# AD8232_TMP136.net
KiCad netlist of a schematic drawn in Altium Designer
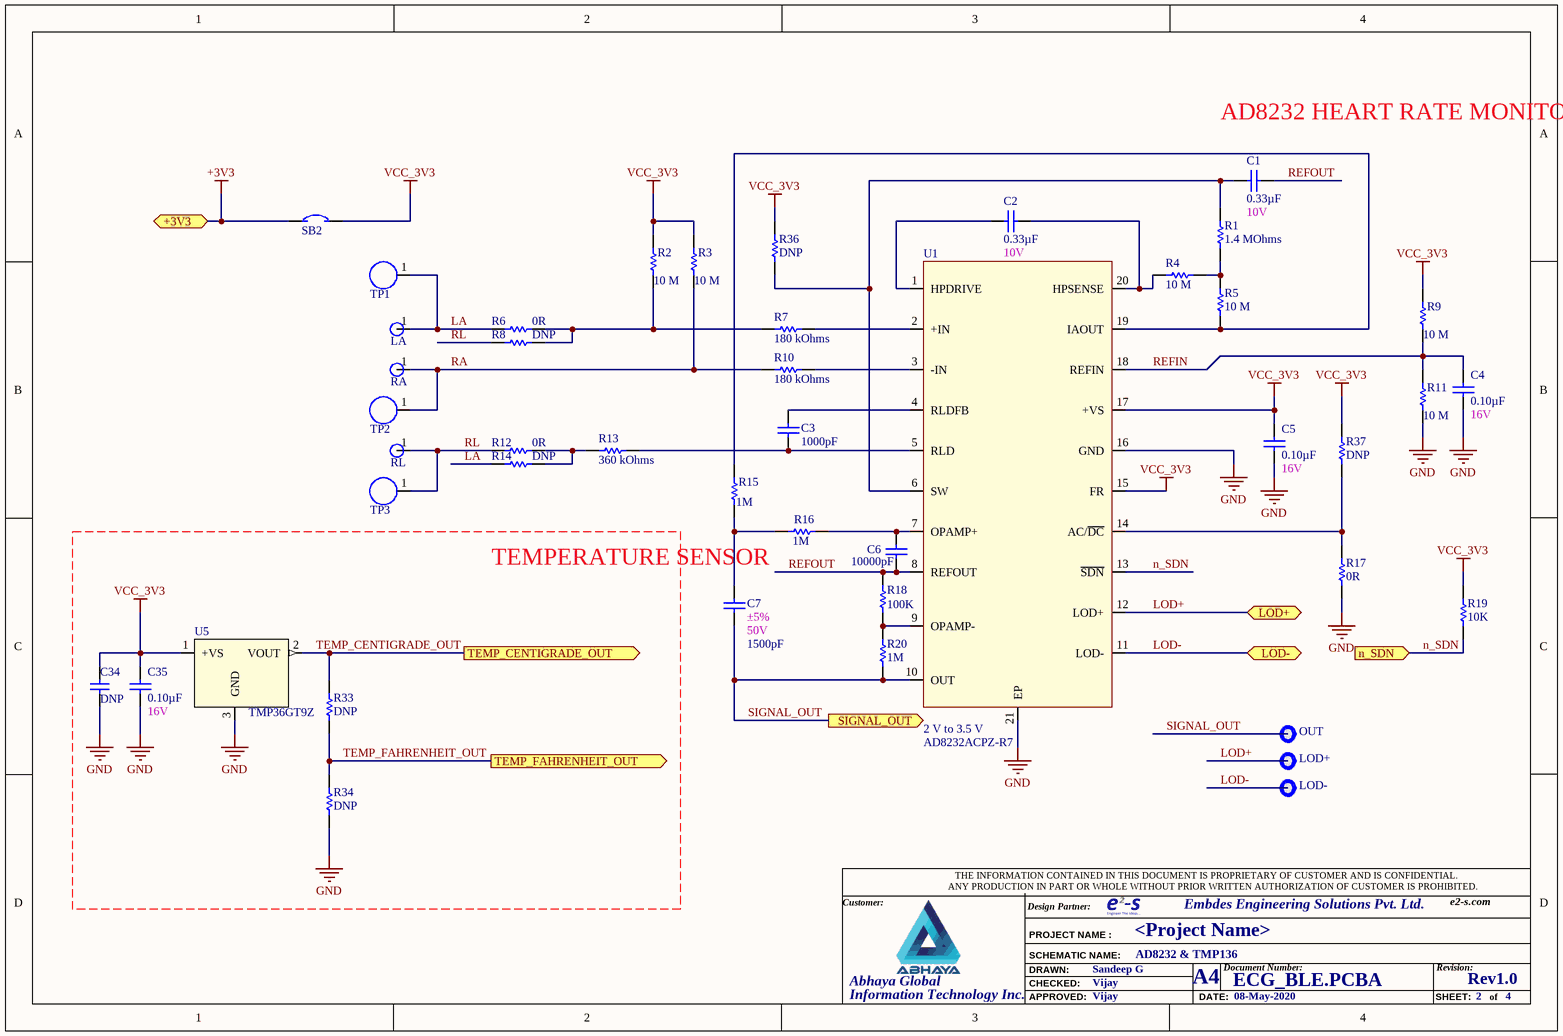
[diagram p0: AD8232 & TMP136.SchDoc]

(export (version "E")
  (design (tool "Eeschema 10.0.6"))
  (components
    (comp (ref "C1")
      (value "0.33µF")
      (footprint "SMDC0402")
      (description "CAP CER 0.33UF 10V X5R 0402")
      (fields
        (field (name "MANUFACTURER") "Samsung Electro-Mechanics")
        (field (name "MANUFACTURER PART NUMBER") "CL05A334KP5NNNC")
        (field (name "1ST AUXILIARY FIELD") "10V")
      )
      (libsource (lib "Master_ Library") (part "ECA0U33L10V0-SB"))
    )
    (comp (ref "C2")
      (value "0.33µF")
      (footprint "SMDC0402")
      (description "CAP CER 0.33UF 10V X5R 0402")
      (fields
        (field (name "MANUFACTURER") "Samsung Electro-Mechanics")
        (field (name "MANUFACTURER PART NUMBER") "CL05A334KP5NNNC")
        (field (name "1ST AUXILIARY FIELD") "10V")
      )
      (libsource (lib "Master_ Library") (part "ECA0U33L10V0-SB"))
    )
    (comp (ref "C3")
      (value "1000pF")
      (footprint "SMDC0402")
      (description "CAP CER 1000PF 50V X7R 0402")
      (fields
        (field (name "MANUFACTURER") "KEMET")
        (field (name "MANUFACTURER PART NUMBER") "C0402C102J5RACTU")
      )
      (libsource (lib "Master_ Library") (part "ECA1N00K50V0-SB"))
    )
    (comp (ref "C4")
      (value "0.10µF")
      (footprint "SMDC0402")
      (description "CAP CER 0.1UF 16V X7R 0402")
      (fields
        (field (name "MANUFACTURER") "Samsung Electro-Mechanics America, Inc.")
        (field (name "MANUFACTURER PART NUMBER") "CL05B104KO5NNNC")
        (field (name "1ST AUXILIARY FIELD") "16V")
      )
      (libsource (lib "Master_ Library") (part "ECA0U10K16V0-1-SB"))
    )
    (comp (ref "C5")
      (value "0.10µF")
      (footprint "SMDC0402")
      (description "CAP CER 0.1UF 16V X7R 0402")
      (fields
        (field (name "MANUFACTURER") "Samsung Electro-Mechanics America, Inc.")
        (field (name "MANUFACTURER PART NUMBER") "CL05B104KO5NNNC")
        (field (name "1ST AUXILIARY FIELD") "16V")
      )
      (libsource (lib "Master_ Library") (part "ECA0U10K16V0-1-SB"))
    )
    (comp (ref "C6")
      (value "10000pF")
      (footprint "SMDCC0402")
      (description "CAP CER 10000PF 50V X7R 0402")
      (fields
        (field (name "MANUFACTURER PART NUMBER") "C0402C103J5RACTU")
        (field (name "MANUFACTURER") "Samsung Electro-Mechanics America, Inc.")
      )
      (libsource (lib "Master_ Library") (part "ECA10N0K50V0-SB"))
    )
    (comp (ref "C7")
      (value "1500pF")
      (footprint "SMDC0402")
      (description "CAP CER 1500PF 50V X7R 0402")
      (fields
        (field (name "MANUFACTURER") "Yageo")
        (field (name "VENDOR PART NUMBER") "311-3763-1-ND")
        (field (name "2ND AUXILIARY FIELD") "±5%")
        (field (name "1ST AUXILIARY FIELD") "50V")
      )
      (libsource (lib "Master_ Library") (part "ECA1N50K50V0-SB"))
    )
    (comp (ref "C34")
      (value "DNP")
      (footprint "SMDC0402")
      (description "CAP CER 2.2UF 10V JB 0402")
      (fields
        (field (name "INTERNAL PART NUMBER") "ECA2U20L10V-SB")
        (field (name "MANUFACTURER") "TDK Corporation")
      )
      (libsource (lib "Master_ Library") (part "ECA2U20L10V-SB"))
    )
    (comp (ref "C35")
      (value "0.10µF")
      (footprint "SMDC0402")
      (description "CAP CER 0.1UF 16V X7R 0402")
      (fields
        (field (name "MANUFACTURER") "Samsung Electro-Mechanics America, Inc.")
        (field (name "MANUFACTURER PART NUMBER") "CL05B104KO5NNNC")
        (field (name "1ST AUXILIARY FIELD") "16V")
      )
      (libsource (lib "Master_ Library") (part "ECA0U10K16V0-1-SB"))
    )
    (comp (ref "LA")
      (value "Test Point- 1.02mm Hole, 1.52mm Round Pad")
      (footprint "TP_1.02X1.52MM_TH")
      (fields (field (name "INTERNAL PART NUMBER") "EMS-TP_1X1.52MM_TH"))
      (libsource (lib "Integrated_Library (1)") (part "EMS-TP_1X1.52MM_TH"))
    )
    (comp (ref "LOD+")
      (value "TEST POINT")
      (footprint "TP_40X40")
      (fields (field (name "INTERNAL PART NUMBER") "EMS-TP40X40-S"))
      (libsource (lib "Integrated_Master_Library") (part "EMS-TP40X40-S"))
    )
    (comp (ref "LOD-")
      (value "TEST POINT")
      (footprint "TP_40X40")
      (fields (field (name "INTERNAL PART NUMBER") "EMS-TP40X40-S"))
      (libsource (lib "Integrated_Master_Library") (part "EMS-TP40X40-S"))
    )
    (comp (ref "OUT")
      (value "TEST POINT")
      (footprint "TP_40X40")
      (fields (field (name "INTERNAL PART NUMBER") "EMS-TP40X40-S"))
      (libsource (lib "Integrated_Master_Library") (part "EMS-TP40X40-S"))
    )
    (comp (ref "R1")
      (value "1.4 MOhms")
      (footprint "SMDR0402")
      (description "RES 1.4M OHM 1% 1/16W 0402")
      (fields
        (field (name "MANUFACTURER") "Stackpole Electronics Inc")
        (field (name "VENDOR PART NUMBER") "RMCF0402FT1M40CT-ND")
      )
      (libsource (lib "Master_ Library") (part "ERE1M40G116-SB"))
    )
    (comp (ref "R2")
      (value "10 M")
      (footprint "SMDR0402")
      (description "RES SMD 10M OHM 5% 1/10W 0402")
      (fields
        (field (name "MANUFACTURER PART NUMBER") "ERJ-2GEJ106X")
        (field (name "MANUFACTURER") "Panasonic Electronic Components")
      )
      (libsource (lib "Master_ Library") (part "ERE10M0K110-SB"))
    )
    (comp (ref "R3")
      (value "10 M")
      (footprint "SMDR0402")
      (description "RES SMD 10M OHM 5% 1/10W 0402")
      (fields
        (field (name "MANUFACTURER PART NUMBER") "ERJ-2GEJ106X")
        (field (name "MANUFACTURER") "Panasonic Electronic Components")
      )
      (libsource (lib "Master_ Library") (part "ERE10M0K110-SB"))
    )
    (comp (ref "R4")
      (value "10 M")
      (footprint "SMDR0402")
      (description "RES SMD 10M OHM 5% 1/10W 0402")
      (fields
        (field (name "MANUFACTURER PART NUMBER") "ERJ-2GEJ106X")
        (field (name "MANUFACTURER") "Panasonic Electronic Components")
      )
      (libsource (lib "Master_ Library") (part "ERE10M0K110-SB"))
    )
    (comp (ref "R5")
      (value "10 M")
      (footprint "SMDR0402")
      (description "RES SMD 10M OHM 5% 1/10W 0402")
      (fields
        (field (name "MANUFACTURER PART NUMBER") "ERJ-2GEJ106X")
        (field (name "MANUFACTURER") "Panasonic Electronic Components")
      )
      (libsource (lib "Master_ Library") (part "ERE10M0K110-SB"))
    )
    (comp (ref "R6")
      (value "0R")
      (footprint "SMDR0402")
      (description "RES SMD 0.0OHM JUMPER 1/10W 0402")
      (fields
        (field (name "MANUFACTURER") "Panasonic Electronic Components")
        (field (name "VENDOR PART NUMBER") "P0.0JCT-ND")
      )
      (libsource (lib "Integrated_Master_Library") (part "ERE0R00110-SB"))
    )
    (comp (ref "R7")
      (value "180 kOhms")
      (footprint "SMDR0402")
      (description "RES SMD 180K OHM 1% 1/16W 0402")
      (fields (field (name "MANUFACTURER") "Yageo") (field (name "VENDOR PART NUMBER") "311-180KLRCT-ND"))
      (libsource (lib "Master_ Library") (part "ERE180KG116-SB"))
    )
    (comp (ref "R8")
      (value "DNP")
      (footprint "SMDR0402")
      (description "RES SMD 0.0OHM JUMPER 1/10W 0402")
      (fields
        (field (name "MANUFACTURER") "Panasonic Electronic Components")
        (field (name "VENDOR PART NUMBER") "P0.0JCT-ND")
      )
      (libsource (lib "Integrated_Master_Library") (part "ERE0R00110-SB"))
    )
    (comp (ref "R9")
      (value "10 M")
      (footprint "SMDR0402")
      (description "RES SMD 10M OHM 5% 1/10W 0402")
      (fields
        (field (name "MANUFACTURER PART NUMBER") "ERJ-2GEJ106X")
        (field (name "MANUFACTURER") "Panasonic Electronic Components")
      )
      (libsource (lib "Master_ Library") (part "ERE10M0K110-SB"))
    )
    (comp (ref "R10")
      (value "180 kOhms")
      (footprint "SMDR0402")
      (description "RES SMD 180K OHM 1% 1/16W 0402")
      (fields (field (name "MANUFACTURER") "Yageo") (field (name "VENDOR PART NUMBER") "311-180KLRCT-ND"))
      (libsource (lib "Master_ Library") (part "ERE180KG116-SB"))
    )
    (comp (ref "R11")
      (value "10 M")
      (footprint "SMDR0402")
      (description "RES SMD 10M OHM 5% 1/10W 0402")
      (fields
        (field (name "MANUFACTURER PART NUMBER") "ERJ-2GEJ106X")
        (field (name "MANUFACTURER") "Panasonic Electronic Components")
      )
      (libsource (lib "Master_ Library") (part "ERE10M0K110-SB"))
    )
    (comp (ref "R12")
      (value "0R")
      (footprint "SMDR0402")
      (description "RES SMD 0.0OHM JUMPER 1/10W 0402")
      (fields
        (field (name "MANUFACTURER") "Panasonic Electronic Components")
        (field (name "VENDOR PART NUMBER") "P0.0JCT-ND")
      )
      (libsource (lib "Integrated_Master_Library") (part "ERE0R00110-SB"))
    )
    (comp (ref "R13")
      (value "360 kOhms")
      (footprint "SMDR0402")
      (description "RES SMD 360K OHM 1% 1/10W 0402")
      (fields
        (field (name "MANUFACTURER") "Panasonic Electronic Components")
        (field (name "VENDOR PART NUMBER") "P360KLCT-ND")
      )
      (libsource (lib "Master_ Library") (part "ERE360KG110-SB"))
    )
    (comp (ref "R14")
      (value "DNP")
      (footprint "SMDR0402")
      (description "RES SMD 0.0OHM JUMPER 1/10W 0402")
      (fields
        (field (name "MANUFACTURER") "Panasonic Electronic Components")
        (field (name "VENDOR PART NUMBER") "P0.0JCT-ND")
      )
      (libsource (lib "Integrated_Master_Library") (part "ERE0R00110-SB"))
    )
    (comp (ref "R15")
      (value "1M")
      (footprint "SMDR0402")
      (description "RES SMD 1M OHM 1% 1/10W 0402")
      (fields
        (field (name "MANUFACTURER PART NUMBER") "ERJ-2RKF1004X")
        (field (name "MANUFACTURER") "Panasonic Electronic Components")
      )
      (libsource (lib "Master_ Library") (part "ERE1M00G110-SB"))
    )
    (comp (ref "R16")
      (value "1M")
      (footprint "SMDR0402")
      (description "RES SMD 1M OHM 1% 1/10W 0402")
      (fields
        (field (name "MANUFACTURER PART NUMBER") "ERJ-2RKF1004X")
        (field (name "MANUFACTURER") "Panasonic Electronic Components")
      )
      (libsource (lib "Master_ Library") (part "ERE1M00G110-SB"))
    )
    (comp (ref "R17")
      (value "0R")
      (footprint "SMDR0402")
      (description "RES SMD 0.0OHM JUMPER 1/10W 0402")
      (fields
        (field (name "MANUFACTURER") "Panasonic Electronic Components")
        (field (name "VENDOR PART NUMBER") "P0.0JCT-ND")
      )
      (libsource (lib "Integrated_Master_Library") (part "ERE0R00110-SB"))
    )
    (comp (ref "R18")
      (value "100K")
      (footprint "SMDRC0402")
      (description "RES SMD 100K OHM 1% 1/10W 0402")
      (fields
        (field (name "MANUFACTURER PART NUMBER") "ERJ-2RKF1003X")
        (field (name "MANUFACTURER") "Panasonic Electronic Components")
      )
      (libsource (lib "Master_ Library") (part "ERE100KG110-SB"))
    )
    (comp (ref "R19")
      (value "10K")
      (footprint "SMDR0402")
      (description "RES SMD 10K OHM 1% 1/10W 0402")
      (fields
        (field (name "MANUFACTURER") "Panasonic Electronic Components")
        (field (name "INTERNAL PART NUMBER") "ERE10K0G110-SB")
      )
      (libsource (lib "Master_ Library") (part "ERE10K0G110-SB"))
    )
    (comp (ref "R20")
      (value "1M")
      (footprint "SMDR0402")
      (description "RES SMD 1M OHM 1% 1/10W 0402")
      (fields
        (field (name "MANUFACTURER PART NUMBER") "ERJ-2RKF1004X")
        (field (name "MANUFACTURER") "Panasonic Electronic Components")
      )
      (libsource (lib "Master_ Library") (part "ERE1M00G110-SB"))
    )
    (comp (ref "R33")
      (value "DNP")
      (footprint "SMDR0402")
      (description "RES 45.3K OHM 0.5% 1/16W 0402")
      (fields
        (field (name "MANUFACTURER") "Stackpole Electronics Inc")
        (field (name "VENDOR PART NUMBER") "RNCF0402DTE45K3CT-ND")
      )
      (libsource (lib "Master_ Library") (part "ERE45K3F116-SB"))
    )
    (comp (ref "R34")
      (value "DNP")
      (footprint "SMDR0402")
      (description "RES SMD 10K OHM 0.5% 1/16W 0402")
      (fields
        (field (name "MANUFACTURER") "Panasonic Electronic Components")
        (field (name "VENDOR PART NUMBER") "P15984CT-ND")
      )
      (libsource (lib "Master_ Library") (part "ERE10K0F116-SB"))
    )
    (comp (ref "R36")
      (value "DNP")
      (footprint "SMDR0402")
      (description "RES SMD 0.0OHM JUMPER 1/10W 0402")
      (fields
        (field (name "MANUFACTURER") "Panasonic Electronic Components")
        (field (name "VENDOR PART NUMBER") "P0.0JCT-ND")
      )
      (libsource (lib "Integrated_Master_Library") (part "ERE0R00110-SB"))
    )
    (comp (ref "R37")
      (value "DNP")
      (footprint "SMDR0402")
      (description "RES SMD 0.0OHM JUMPER 1/10W 0402")
      (fields
        (field (name "MANUFACTURER") "Panasonic Electronic Components")
        (field (name "VENDOR PART NUMBER") "P0.0JCT-ND")
      )
      (libsource (lib "Integrated_Master_Library") (part "ERE0R00110-SB"))
    )
    (comp (ref "RA")
      (value "Test Point- 1.02mm Hole, 1.52mm Round Pad")
      (footprint "TP_1.02X1.52MM_TH")
      (fields (field (name "INTERNAL PART NUMBER") "EMS-TP_1X1.52MM_TH"))
      (libsource (lib "Integrated_Library (1)") (part "EMS-TP_1X1.52MM_TH"))
    )
    (comp (ref "RL")
      (value "Test Point- 1.02mm Hole, 1.52mm Round Pad")
      (footprint "TP_1.02X1.52MM_TH")
      (fields (field (name "INTERNAL PART NUMBER") "EMS-TP_1X1.52MM_TH"))
      (libsource (lib "Integrated_Library (1)") (part "EMS-TP_1X1.52MM_TH"))
    )
    (comp (ref "SB2")
      (value "EMS_SB0805")
      (footprint "SB_0805")
      (libsource (lib "Masterlib_auto") (part "EMS_SB0805"))
    )
    (comp (ref "TP1")
      (value "Electrode point")
      (footprint "ELE-MH-6x8MM")
      (fields (field (name "INTERNAL PART NUMBER") "EMS-ELE_6X8MM_TH"))
      (libsource (lib "ECG_BLE") (part "EMS-ELE_6X8MM_TH"))
    )
    (comp (ref "TP2")
      (value "Electrode point")
      (footprint "ELE-MH-6x8MM")
      (fields (field (name "INTERNAL PART NUMBER") "EMS-ELE_6X8MM_TH"))
      (libsource (lib "ECG_BLE") (part "EMS-ELE_6X8MM_TH"))
    )
    (comp (ref "TP3")
      (value "Electrode point")
      (footprint "ELE-MH-6x8MM")
      (fields (field (name "INTERNAL PART NUMBER") "EMS-ELE_6X8MM_TH"))
      (libsource (lib "ECG_BLE") (part "EMS-ELE_6X8MM_TH"))
    )
    (comp (ref "U1")
      (value "AD8232ACPZ-R7")
      (footprint "QFN50P400X400X80_HS-21N")
      (description "Analog Front End - AFE ECG and HRM IC Single Lead")
      (fields
        (field (name "INTERNAL PART NUMBER") "EICADLFCSP-20-1862")
        (field (name "MANUFACTURER") "Analog Devices")
        (field (name "1ST AUXILIARY FIELD") "2 V to 3.5 V")
      )
      (libsource (lib "Master_ Library") (part "EICADLFCSP-20-1862"))
    )
    (comp (ref "U5")
      (value "TMP36GT9Z")
      (footprint "TO-226-AA")
      (description "SENSOR ANALOG -40C-125C TO92-3")
      (fields
        (field (name "INTERNAL PART NUMBER") "EICADTO92-3-1865")
        (field (name "MANUFACTURER") "Analog Devices Inc.")
      )
      (libsource (lib "Master_ Library") (part "EICADTO92-3-1865"))
    )
  )
  (nets
    (net (code "1") (name "+3V3") (class "Default")
      (node (ref "SB2") (pin "1") (pinfunction "1_1") (pintype "passive"))
    )
    (net (code "2") (name "/LA") (class "Default")
      (node (ref "LA") (pin "1") (pinfunction "1_1") (pintype "passive"))
      (node (ref "R14") (pin "1") (pinfunction "1_1") (pintype "passive"))
      (node (ref "R6") (pin "1") (pinfunction "1_1") (pintype "passive"))
      (node (ref "TP1") (pin "1") (pinfunction "1_1") (pintype "passive"))
    )
    (net (code "3") (name "/LOD+") (class "Default")
      (node (ref "LOD+") (pin "1") (pinfunction "1_1") (pintype "passive"))
      (node (ref "U1") (pin "12") (pinfunction "LOD+_12") (pintype "passive"))
    )
    (net (code "4") (name "/LOD-") (class "Default")
      (node (ref "LOD-") (pin "1") (pinfunction "1_1") (pintype "passive"))
      (node (ref "U1") (pin "11") (pinfunction "LOD-_11") (pintype "passive"))
    )
    (net (code "5") (name "/RA") (class "Default")
      (node (ref "R10") (pin "1") (pinfunction "1_1") (pintype "passive"))
      (node (ref "R3") (pin "1") (pinfunction "1_1") (pintype "passive"))
      (node (ref "RA") (pin "1") (pinfunction "1_1") (pintype "passive"))
      (node (ref "TP2") (pin "1") (pinfunction "1_1") (pintype "passive"))
    )
    (net (code "6") (name "/REFIN") (class "Default")
      (node (ref "C4") (pin "2") (pinfunction "2_2") (pintype "passive"))
      (node (ref "R11") (pin "2") (pinfunction "2_2") (pintype "passive"))
      (node (ref "R9") (pin "1") (pinfunction "1_1") (pintype "passive"))
      (node (ref "U1") (pin "18") (pinfunction "REFIN_18") (pintype "passive"))
    )
    (net (code "7") (name "/REFOUT") (class "Default")
      (node (ref "C1") (pin "2") (pinfunction "2_2") (pintype "passive"))
      (node (ref "C6") (pin "1") (pinfunction "1_1") (pintype "passive"))
      (node (ref "R18") (pin "1") (pinfunction "1_1") (pintype "passive"))
      (node (ref "U1") (pin "8") (pinfunction "REFOUT_8") (pintype "passive"))
    )
    (net (code "8") (name "/RL") (class "Default")
      (node (ref "R12") (pin "1") (pinfunction "1_1") (pintype "passive"))
      (node (ref "R8") (pin "1") (pinfunction "1_1") (pintype "passive"))
      (node (ref "RL") (pin "1") (pinfunction "1_1") (pintype "passive"))
      (node (ref "TP3") (pin "1") (pinfunction "1_1") (pintype "passive"))
    )
    (net (code "9") (name "/SIGNAL_OUT") (class "Default")
      (node (ref "C7") (pin "1") (pinfunction "1_1") (pintype "passive"))
      (node (ref "OUT") (pin "1") (pinfunction "1_1") (pintype "passive"))
      (node (ref "R20") (pin "2") (pinfunction "2_2") (pintype "passive"))
      (node (ref "U1") (pin "10") (pinfunction "OUT_10") (pintype "passive"))
    )
    (net (code "10") (name "/TEMP_CENTIGRADE_OUT") (class "Default")
      (node (ref "R33") (pin "2") (pinfunction "2_2") (pintype "passive"))
      (node (ref "U5") (pin "2") (pinfunction "VOUT_2") (pintype "output"))
    )
    (net (code "11") (name "/TEMP_FAHRENHEIT_OUT") (class "Default")
      (node (ref "R33") (pin "1") (pinfunction "1_1") (pintype "passive"))
      (node (ref "R34") (pin "2") (pinfunction "2_2") (pintype "passive"))
    )
    (net (code "12") (name "/n_SDN") (class "Default")
      (node (ref "R19") (pin "2") (pinfunction "2_2") (pintype "passive"))
      (node (ref "U1") (pin "13") (pinfunction "~{SDN}_13") (pintype "passive"))
    )
    (net (code "13") (name "GND") (class "Default")
      (node (ref "C34") (pin "1") (pinfunction "1_1") (pintype "passive"))
      (node (ref "C35") (pin "1") (pinfunction "1_1") (pintype "passive"))
      (node (ref "C4") (pin "1") (pinfunction "1_1") (pintype "passive"))
      (node (ref "C5") (pin "1") (pinfunction "1_1") (pintype "passive"))
      (node (ref "R11") (pin "1") (pinfunction "1_1") (pintype "passive"))
      (node (ref "R17") (pin "2") (pinfunction "2_2") (pintype "passive"))
      (node (ref "R34") (pin "1") (pinfunction "1_1") (pintype "passive"))
      (node (ref "U1") (pin "16") (pinfunction "GND_16") (pintype "passive"))
      (node (ref "U1") (pin "21") (pinfunction "EP_21") (pintype "passive"))
      (node (ref "U5") (pin "3") (pinfunction "GND_3") (pintype "power_in"))
    )
    (net (code "14") (name "Net-(C7-Pad2)") (class "Default")
      (node (ref "C7") (pin "2") (pinfunction "2_2") (pintype "passive"))
      (node (ref "R15") (pin "1") (pinfunction "1_1") (pintype "passive"))
      (node (ref "R16") (pin "2") (pinfunction "2_2") (pintype "passive"))
    )
    (net (code "15") (name "Net-(R1-Pad1)") (class "Default")
      (node (ref "R1") (pin "1") (pinfunction "1_1") (pintype "passive"))
      (node (ref "R4") (pin "1") (pinfunction "1_1") (pintype "passive"))
      (node (ref "R5") (pin "1") (pinfunction "1_1") (pintype "passive"))
    )
    (net (code "16") (name "Net-(R2-Pad1)") (class "Default")
      (node (ref "R2") (pin "1") (pinfunction "1_1") (pintype "passive"))
      (node (ref "R6") (pin "2") (pinfunction "2_2") (pintype "passive"))
      (node (ref "R7") (pin "1") (pinfunction "1_1") (pintype "passive"))
      (node (ref "R8") (pin "2") (pinfunction "2_2") (pintype "passive"))
    )
    (net (code "17") (name "Net-(R12-Pad2)") (class "Default")
      (node (ref "R12") (pin "2") (pinfunction "2_2") (pintype "passive"))
      (node (ref "R13") (pin "1") (pinfunction "1_1") (pintype "passive"))
      (node (ref "R14") (pin "2") (pinfunction "2_2") (pintype "passive"))
    )
    (net (code "18") (name "Net-(U1-+IN)") (class "Default")
      (node (ref "R7") (pin "2") (pinfunction "2_2") (pintype "passive"))
      (node (ref "U1") (pin "2") (pinfunction "+IN_2") (pintype "passive"))
    )
    (net (code "19") (name "Net-(U1--IN)") (class "Default")
      (node (ref "R10") (pin "2") (pinfunction "2_2") (pintype "passive"))
      (node (ref "U1") (pin "3") (pinfunction "-IN_3") (pintype "passive"))
    )
    (net (code "20") (name "Net-(U1-AC{slash}~{DC})") (class "Default")
      (node (ref "R17") (pin "1") (pinfunction "1_1") (pintype "passive"))
      (node (ref "R37") (pin "2") (pinfunction "2_2") (pintype "passive"))
      (node (ref "U1") (pin "14") (pinfunction "AC/~{DC}_14") (pintype "passive"))
    )
    (net (code "21") (name "Net-(U1-HPDRIVE)") (class "Default")
      (node (ref "C2") (pin "1") (pinfunction "1_1") (pintype "passive"))
      (node (ref "U1") (pin "1") (pinfunction "HPDRIVE_1") (pintype "passive"))
    )
    (net (code "22") (name "Net-(U1-HPSENSE)") (class "Default")
      (node (ref "C2") (pin "2") (pinfunction "2_2") (pintype "passive"))
      (node (ref "R4") (pin "2") (pinfunction "2_2") (pintype "passive"))
      (node (ref "U1") (pin "20") (pinfunction "HPSENSE_20") (pintype "passive"))
    )
    (net (code "23") (name "Net-(U1-IAOUT)") (class "Default")
      (node (ref "R15") (pin "2") (pinfunction "2_2") (pintype "passive"))
      (node (ref "R5") (pin "2") (pinfunction "2_2") (pintype "passive"))
      (node (ref "U1") (pin "19") (pinfunction "IAOUT_19") (pintype "passive"))
    )
    (net (code "24") (name "Net-(U1-OPAMP+)") (class "Default")
      (node (ref "C6") (pin "2") (pinfunction "2_2") (pintype "passive"))
      (node (ref "R16") (pin "1") (pinfunction "1_1") (pintype "passive"))
      (node (ref "U1") (pin "7") (pinfunction "OPAMP+_7") (pintype "passive"))
    )
    (net (code "25") (name "Net-(U1-OPAMP-)") (class "Default")
      (node (ref "R18") (pin "2") (pinfunction "2_2") (pintype "passive"))
      (node (ref "R20") (pin "1") (pinfunction "1_1") (pintype "passive"))
      (node (ref "U1") (pin "9") (pinfunction "OPAMP-_9") (pintype "passive"))
    )
    (net (code "26") (name "Net-(U1-RLD)") (class "Default")
      (node (ref "C3") (pin "1") (pinfunction "1_1") (pintype "passive"))
      (node (ref "R13") (pin "2") (pinfunction "2_2") (pintype "passive"))
      (node (ref "U1") (pin "5") (pinfunction "RLD_5") (pintype "passive"))
    )
    (net (code "27") (name "Net-(U1-RLDFB)") (class "Default")
      (node (ref "C3") (pin "2") (pinfunction "2_2") (pintype "passive"))
      (node (ref "U1") (pin "4") (pinfunction "RLDFB_4") (pintype "passive"))
    )
    (net (code "28") (name "Net-(U1-SW)") (class "Default")
      (node (ref "C1") (pin "1") (pinfunction "1_1") (pintype "passive"))
      (node (ref "R1") (pin "2") (pinfunction "2_2") (pintype "passive"))
      (node (ref "R36") (pin "1") (pinfunction "1_1") (pintype "passive"))
      (node (ref "U1") (pin "6") (pinfunction "SW_6") (pintype "passive"))
    )
    (net (code "29") (name "VCC_3V3") (class "Default")
      (node (ref "C34") (pin "2") (pinfunction "2_2") (pintype "passive"))
      (node (ref "C35") (pin "2") (pinfunction "2_2") (pintype "passive"))
      (node (ref "C5") (pin "2") (pinfunction "2_2") (pintype "passive"))
      (node (ref "R19") (pin "1") (pinfunction "1_1") (pintype "passive"))
      (node (ref "R2") (pin "2") (pinfunction "2_2") (pintype "passive"))
      (node (ref "R3") (pin "2") (pinfunction "2_2") (pintype "passive"))
      (node (ref "R36") (pin "2") (pinfunction "2_2") (pintype "passive"))
      (node (ref "R37") (pin "1") (pinfunction "1_1") (pintype "passive"))
      (node (ref "R9") (pin "2") (pinfunction "2_2") (pintype "passive"))
      (node (ref "SB2") (pin "2") (pinfunction "2_2") (pintype "passive"))
      (node (ref "U1") (pin "15") (pinfunction "FR_15") (pintype "passive"))
      (node (ref "U1") (pin "17") (pinfunction "+VS_17") (pintype "passive"))
      (node (ref "U5") (pin "1") (pinfunction "+VS_1") (pintype "power_in"))
    )
  )
)
